# FIRST_FINAL_CPO.net
KiCad netlist of a schematic drawn in EAGLE
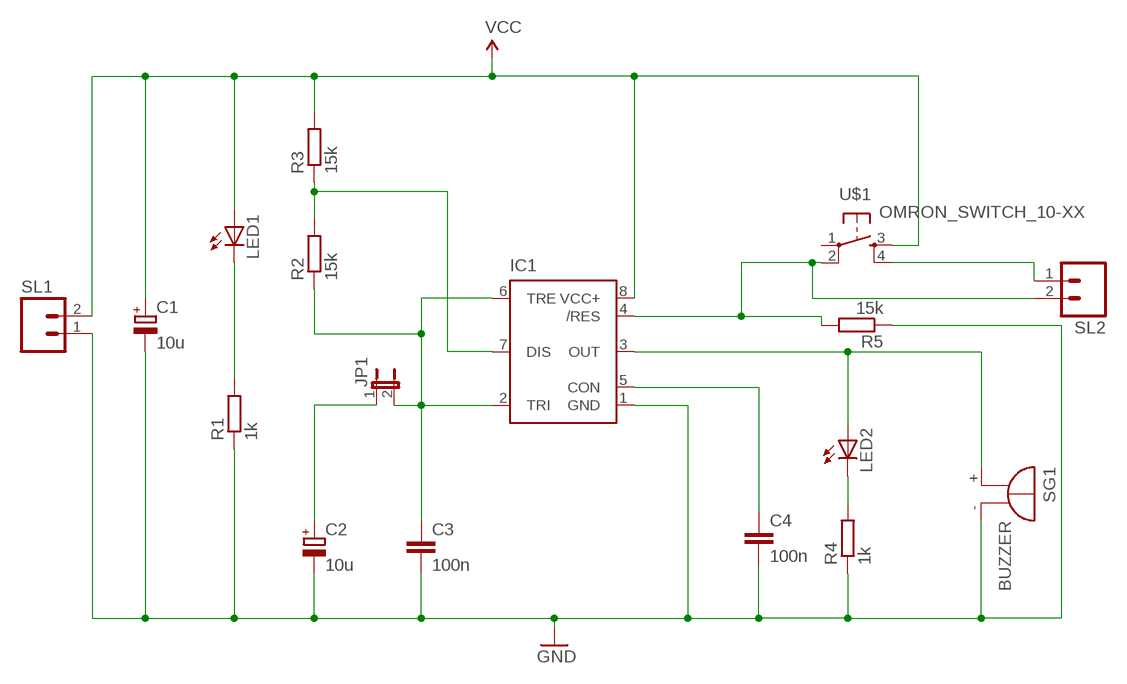
[diagram p0: schematic, sheet 1]

(export (version "E")
  (design (tool "Eeschema 10.0.6"))
  (components
    (comp (ref "C1")
      (value "10u")
      (footprint "eagle-import:E2,5-5")
      (libsource (lib "eagle-import") (part "CPOL-EUE2.5-5"))
    )
    (comp (ref "C2")
      (value "10u")
      (footprint "eagle-import:E2,5-5")
      (libsource (lib "eagle-import") (part "CPOL-EUE2.5-5"))
    )
    (comp (ref "C3")
      (value "100n")
      (footprint "eagle-import:C025-025X050")
      (libsource (lib "eagle-import") (part "C-EU025-025X050"))
    )
    (comp (ref "C4")
      (value "100n")
      (footprint "eagle-import:C025-025X050")
      (libsource (lib "eagle-import") (part "C-EU025-025X050"))
    )
    (comp (ref "IC1")
      (value "NE555P")
      (footprint "eagle-import:DIL-08")
      (fields (field (name "MF") "Arrow Electronics") (field (name "MPN") "NE555N"))
      (libsource (lib "eagle-import") (part "NE555P"))
    )
    (comp (ref "JP1")
      (value "JP1E")
      (footprint "eagle-import:JP1")
      (libsource (lib "eagle-import") (part "JP1E"))
    )
    (comp (ref "LED1")
      (value "LED5MM")
      (footprint "eagle-import:LED5MM")
      (libsource (lib "eagle-import") (part "LED5MM"))
    )
    (comp (ref "LED2")
      (value "LED5MM")
      (footprint "eagle-import:LED5MM")
      (libsource (lib "eagle-import") (part "LED5MM"))
    )
    (comp (ref "R1")
      (value "1k")
      (footprint "eagle-import:0207_7")
      (libsource (lib "eagle-import") (part "R-EU_0207/7"))
    )
    (comp (ref "R2")
      (value "15k")
      (footprint "eagle-import:0207_7")
      (libsource (lib "eagle-import") (part "R-EU_0207/7"))
    )
    (comp (ref "R3")
      (value "15k")
      (footprint "eagle-import:0207_7")
      (libsource (lib "eagle-import") (part "R-EU_0207/7"))
    )
    (comp (ref "R4")
      (value "1k")
      (footprint "eagle-import:0207_7")
      (libsource (lib "eagle-import") (part "R-EU_0207/7"))
    )
    (comp (ref "R5")
      (value "15k")
      (footprint "eagle-import:0207_7")
      (libsource (lib "eagle-import") (part "R-EU_0207/7"))
    )
    (comp (ref "SG1")
      (value "BUZZER")
      (footprint "eagle-import:F_TMB")
      (libsource (lib "eagle-import") (part "BUZZER"))
    )
    (comp (ref "SL1")
      (value "M02")
      (footprint "eagle-import:02P")
      (libsource (lib "eagle-import") (part "M02"))
    )
    (comp (ref "SL2")
      (value "M02")
      (footprint "eagle-import:02P")
      (libsource (lib "eagle-import") (part "M02"))
    )
    (comp (ref "U$1")
      (value "OMRON_SWITCH_10-XX")
      (footprint "eagle-import:B3F-10XX")
      (libsource (lib "eagle-import") (part "OMRON_SWITCH_10-XX"))
    )
  )
  (nets
    (net (code "1") (name "GND") (class "Default")
      (node (ref "C1") (pin "-") (pinfunction "-_-") (pintype "passive"))
      (node (ref "C2") (pin "-") (pinfunction "-_-") (pintype "passive"))
      (node (ref "C3") (pin "2") (pinfunction "2_2") (pintype "passive"))
      (node (ref "C4") (pin "2") (pinfunction "2_2") (pintype "passive"))
      (node (ref "IC1") (pin "1") (pinfunction "GND_1") (pintype "power_in"))
      (node (ref "R1") (pin "1") (pinfunction "1_1") (pintype "passive"))
      (node (ref "R4") (pin "1") (pinfunction "1_1") (pintype "passive"))
      (node (ref "R5") (pin "1") (pinfunction "1_1") (pintype "passive"))
      (node (ref "SG1") (pin "-") (pinfunction "-_-") (pintype "passive"))
      (node (ref "SL1") (pin "1") (pinfunction "1_1") (pintype "passive"))
    )
    (net (code "2") (name "Net-(C2-Pad+)") (class "Default")
      (node (ref "C2") (pin "+") (pinfunction "+_+") (pintype "passive"))
      (node (ref "JP1") (pin "1") (pinfunction "1_1") (pintype "passive"))
    )
    (net (code "3") (name "Net-(IC1-CON)") (class "Default")
      (node (ref "C4") (pin "1") (pinfunction "1_1") (pintype "passive"))
      (node (ref "IC1") (pin "5") (pinfunction "CON_5") (pintype "input"))
    )
    (net (code "4") (name "Net-(IC1-DIS)") (class "Default")
      (node (ref "IC1") (pin "7") (pinfunction "DIS_7") (pintype "input"))
      (node (ref "R2") (pin "2") (pinfunction "2_2") (pintype "passive"))
      (node (ref "R3") (pin "1") (pinfunction "1_1") (pintype "passive"))
    )
    (net (code "5") (name "Net-(IC1-OUT)") (class "Default")
      (node (ref "IC1") (pin "3") (pinfunction "OUT_3") (pintype "output"))
      (node (ref "LED2") (pin "A") (pinfunction "A_A") (pintype "passive"))
      (node (ref "SG1") (pin "+") (pinfunction "+_+") (pintype "passive"))
    )
    (net (code "6") (name "Net-(IC1-TRE)") (class "Default")
      (node (ref "C3") (pin "1") (pinfunction "1_1") (pintype "passive"))
      (node (ref "IC1") (pin "2") (pinfunction "TRI_2") (pintype "input"))
      (node (ref "IC1") (pin "6") (pinfunction "TRE_6") (pintype "input"))
      (node (ref "JP1") (pin "2") (pinfunction "2_2") (pintype "passive"))
      (node (ref "R2") (pin "1") (pinfunction "1_1") (pintype "passive"))
    )
    (net (code "7") (name "Net-(IC1-{slash}RES)") (class "Default")
      (node (ref "IC1") (pin "4") (pinfunction "/RES_4") (pintype "input"))
      (node (ref "R5") (pin "2") (pinfunction "2_2") (pintype "passive"))
      (node (ref "SL2") (pin "2") (pinfunction "2_2") (pintype "passive"))
      (node (ref "U$1") (pin "2") (pinfunction "P1_2") (pintype "passive"))
    )
    (net (code "8") (name "Net-(LED1-C)") (class "Default")
      (node (ref "LED1") (pin "K") (pinfunction "C_K") (pintype "passive"))
      (node (ref "R1") (pin "2") (pinfunction "2_2") (pintype "passive"))
    )
    (net (code "9") (name "Net-(LED2-C)") (class "Default")
      (node (ref "LED2") (pin "K") (pinfunction "C_K") (pintype "passive"))
      (node (ref "R4") (pin "2") (pinfunction "2_2") (pintype "passive"))
    )
    (net (code "10") (name "Net-(U$1-S1)") (class "Default")
      (node (ref "SL2") (pin "1") (pinfunction "1_1") (pintype "passive"))
      (node (ref "U$1") (pin "4") (pinfunction "S1_4") (pintype "passive"))
    )
    (net (code "11") (name "VCC") (class "Default")
      (node (ref "C1") (pin "+") (pinfunction "+_+") (pintype "passive"))
      (node (ref "IC1") (pin "8") (pinfunction "VCC+_8") (pintype "power_in"))
      (node (ref "LED1") (pin "A") (pinfunction "A_A") (pintype "passive"))
      (node (ref "R3") (pin "2") (pinfunction "2_2") (pintype "passive"))
      (node (ref "SL1") (pin "2") (pinfunction "2_2") (pintype "passive"))
      (node (ref "U$1") (pin "3") (pinfunction "S_3") (pintype "passive"))
    )
    (net (code "12") (name "unconnected-(U$1-P-Pad1)") (class "Default")
      (node (ref "U$1") (pin "1") (pinfunction "P_1") (pintype "passive"))
    )
  )
)
